# ESPC3_schematic.net
KiCad netlist of a schematic drawn in Altium Designer
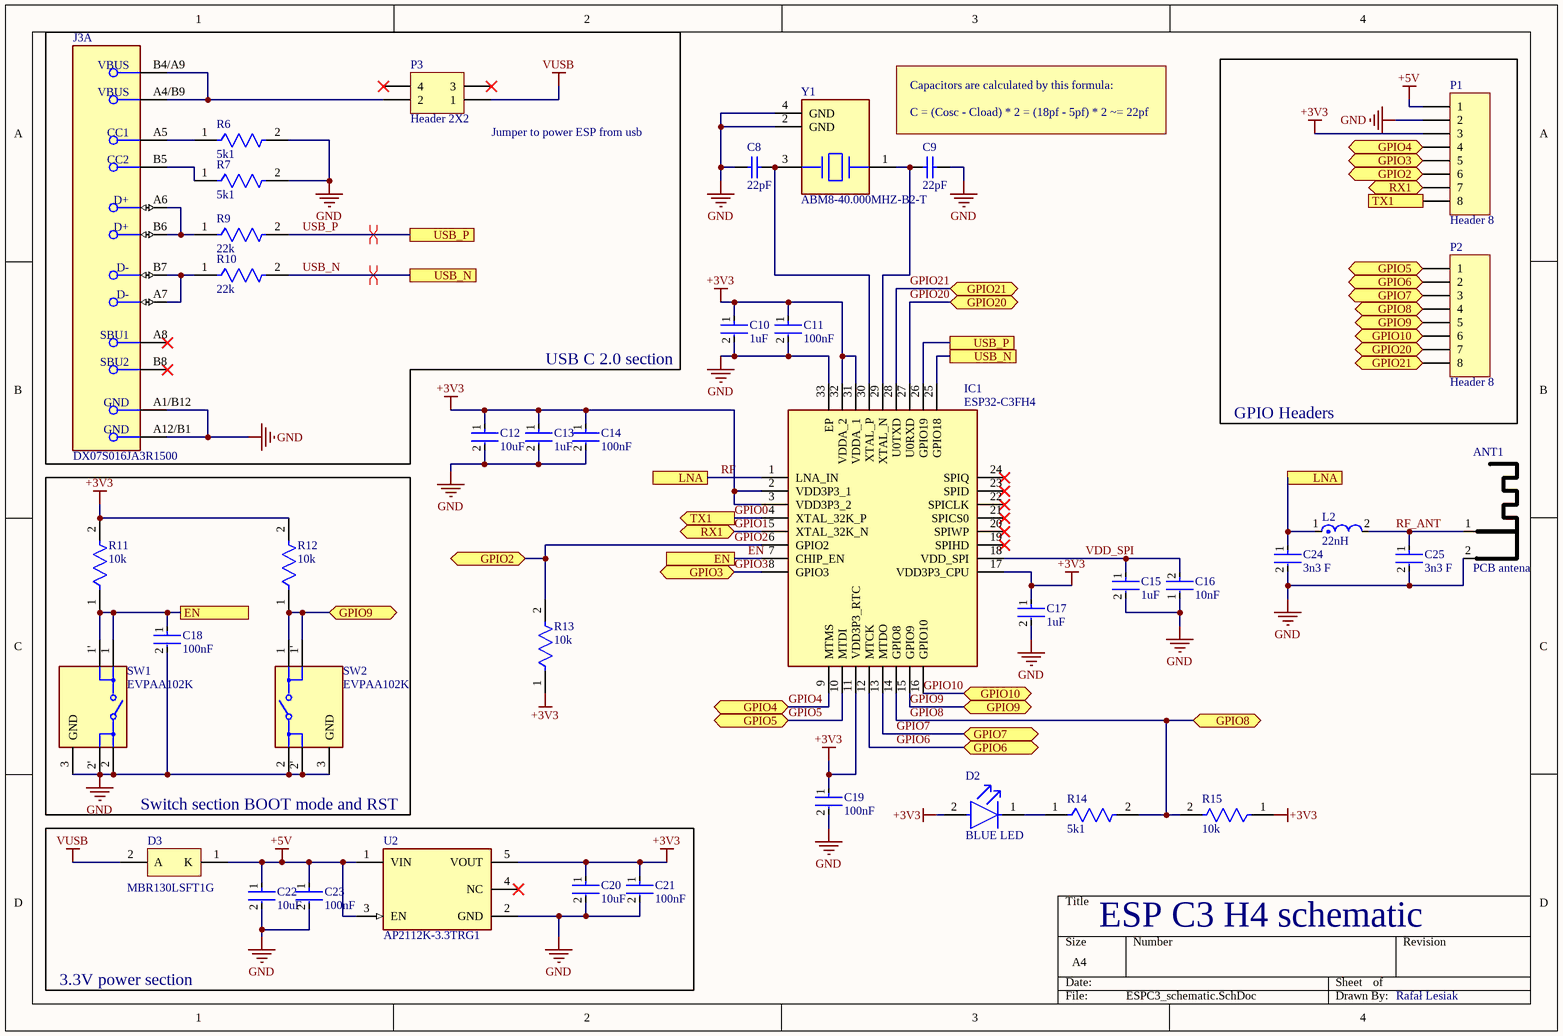
[diagram p0: ESPC3_schematic.SchDoc]

(export (version "E")
  (design (tool "Eeschema 10.0.6"))
  (components
    (comp (ref "ANT1")
      (value "PCB antena")
      (footprint "ANT_PCB_2_4GHz")
      (description "PCB antena 2.4GHz 50ohm from AN043 texas instrument")
      (libsource (lib "ANT_PCB_2_4_GHz") (part "ANT_PCB_2.4GHz"))
    )
    (comp (ref "C8")
      (value "22pF")
      (footprint "CAPC0603X33X15LL03T05")
      (fields
        (field (name "MANUFACTURER") "AVX Interconnect / Elco")
        (field (name "PART NUMBER") "0201YA220JAT2A")
      )
      (libsource (lib "Altium Content Vault") (part "CAP"))
    )
    (comp (ref "C9")
      (value "22pF")
      (footprint "CAPC0603X33X15LL03T05")
      (fields
        (field (name "MANUFACTURER") "AVX Interconnect / Elco")
        (field (name "PART NUMBER") "0201YA220JAT2A")
      )
      (libsource (lib "Altium Content Vault") (part "CAP"))
    )
    (comp (ref "C10")
      (value "1uF")
      (footprint "FP-GRM033-0_05-e01_0_2-MFG")
      (description "Chip Multilayer Ceramic Capacitors for General Purpose, 0201, 1.0uF, X5R, 15%, 20%, 10V")
      (libsource (lib "Altium Content Vault") (part "02cd4be3c70576c341d710602a673aa"))
    )
    (comp (ref "C11")
      (value "100nF")
      (footprint "FP-GRM033-0_03-MFG")
      (description "Chip Multilayer Ceramic Capacitors for General Purpose, 0201, 0.10uF, X7S, 22%, 10%, 10V")
      (fields (field (name "TOLERANCE") "10%"))
      (libsource (lib "Altium Content Vault") (part "b4654b650e69147ec39a6b967a45e02"))
    )
    (comp (ref "C12")
      (value "10uF")
      (footprint "FP-GRM155-0_2-IPC_A")
      (description "Chip Multilayer Ceramic Capacitors for General Purpose, 0402, 10uF, X5R, 15%, 20%, 10V")
      (libsource (lib "Altium Content Vault") (part "b4654b650e69147ec39a6b967a45e02"))
    )
    (comp (ref "C13")
      (value "1uF")
      (footprint "FP-GRM033-0_05-e01_0_2-MFG")
      (description "Chip Multilayer Ceramic Capacitors for General Purpose, 0201, 1.0uF, X5R, 15%, 20%, 10V")
      (libsource (lib "Altium Content Vault") (part "02cd4be3c70576c341d710602a673aa"))
    )
    (comp (ref "C14")
      (value "100nF")
      (footprint "FP-GRM033-0_03-MFG")
      (description "Chip Multilayer Ceramic Capacitors for General Purpose, 0201, 0.10uF, X7S, 22%, 10%, 10V")
      (fields (field (name "TOLERANCE") "10%"))
      (libsource (lib "Altium Content Vault") (part "b4654b650e69147ec39a6b967a45e02"))
    )
    (comp (ref "C15")
      (value "1uF")
      (footprint "FP-GRM033-0_05-e01_0_2-MFG")
      (description "Chip Multilayer Ceramic Capacitors for General Purpose, 0201, 1.0uF, X5R, 15%, 20%, 10V")
      (libsource (lib "Altium Content Vault") (part "02cd4be3c70576c341d710602a673aa"))
    )
    (comp (ref "C16")
      (value "10nF")
      (footprint "FP-GCM033-0_03-MFG")
      (description "Ceramic Capacitor for Automotive 10nF  ±10% 10VDC X7R 0201 Paper T/R")
      (fields (field (name "TOLERANCE") "10%"))
      (libsource (lib "Altium Content Vault") (part "f23184f103b6ebe33a8c269c53dcba6"))
    )
    (comp (ref "C17")
      (value "1uF")
      (footprint "FP-GRM033-0_05-e01_0_2-MFG")
      (description "Chip Multilayer Ceramic Capacitors for General Purpose, 0201, 1.0uF, X5R, 15%, 20%, 10V")
      (libsource (lib "Altium Content Vault") (part "02cd4be3c70576c341d710602a673aa"))
    )
    (comp (ref "C18")
      (value "100nF")
      (footprint "FP-GRM033-0_03-MFG")
      (description "Chip Multilayer Ceramic Capacitors for General Purpose, 0201, 0.10uF, X7S, 22%, 10%, 10V")
      (fields (field (name "TOLERANCE") "10%"))
      (libsource (lib "Altium Content Vault") (part "b4654b650e69147ec39a6b967a45e02"))
    )
    (comp (ref "C19")
      (value "100nF")
      (footprint "FP-GRM033-0_03-MFG")
      (description "Chip Multilayer Ceramic Capacitors for General Purpose, 0201, 0.10uF, X7S, 22%, 10%, 10V")
      (fields (field (name "TOLERANCE") "10%"))
      (libsource (lib "Altium Content Vault") (part "b4654b650e69147ec39a6b967a45e02"))
    )
    (comp (ref "C20")
      (value "10uF")
      (footprint "FP-GRM155-0_2-IPC_A")
      (description "Chip Multilayer Ceramic Capacitors for General Purpose, 0402, 10uF, X5R, 15%, 20%, 10V")
      (libsource (lib "Altium Content Vault") (part "b4654b650e69147ec39a6b967a45e02"))
    )
    (comp (ref "C21")
      (value "100nF")
      (footprint "FP-GRM033-0_03-MFG")
      (description "Chip Multilayer Ceramic Capacitors for General Purpose, 0201, 0.10uF, X7S, 22%, 10%, 10V")
      (fields (field (name "TOLERANCE") "10%"))
      (libsource (lib "Altium Content Vault") (part "b4654b650e69147ec39a6b967a45e02"))
    )
    (comp (ref "C22")
      (value "10uF")
      (footprint "FP-GRM155-0_2-IPC_A")
      (description "Chip Multilayer Ceramic Capacitors for General Purpose, 0402, 10uF, X5R, 15%, 20%, 10V")
      (libsource (lib "Altium Content Vault") (part "b4654b650e69147ec39a6b967a45e02"))
    )
    (comp (ref "C23")
      (value "100nF")
      (footprint "FP-GRM033-0_03-MFG")
      (description "Chip Multilayer Ceramic Capacitors for General Purpose, 0201, 0.10uF, X7S, 22%, 10%, 10V")
      (fields (field (name "TOLERANCE") "10%"))
      (libsource (lib "Altium Content Vault") (part "b4654b650e69147ec39a6b967a45e02"))
    )
    (comp (ref "C24")
      (value "3n3 F")
      (footprint "FP-GRM022-0_02-IPC_C")
      (description "Chip Multilayer Ceramic Capacitors for General Purpose, 01005, 3.3pF, C0G, 30ppm/°C, 0.25pF, 16V")
      (libsource (lib "Altium Content Vault") (part "02cd4be3c70576c341d710602a673aa"))
    )
    (comp (ref "C25")
      (value "3n3 F")
      (footprint "FP-GRM022-0_02-IPC_C")
      (description "Chip Multilayer Ceramic Capacitors for General Purpose, 01005, 3.3pF, C0G, 30ppm/°C, 0.25pF, 16V")
      (libsource (lib "Altium Content Vault") (part "02cd4be3c70576c341d710602a673aa"))
    )
    (comp (ref "D2")
      (value "BLUE LED")
      (footprint "FP-LTST-C191TBKT-MFG")
      (description "LED BLUE CLEAR CHIP SMD")
      (libsource (lib "Altium Content Vault") (part "8706943c75ba83719d021d2fdc84c58"))
    )
    (comp (ref "D3")
      (value "MBR130LSFT1G")
      (footprint "ONSC-SOD-123FL-2-498_V")
      (description "Schottky Power Rectifier, 2-Pin SOD-123, Pb-Free, Tape and Reel")
      (fields (field (name "MANUFACTURER") "On Semiconductor"))
      (libsource (lib "Altium Content Vault") (part "ONSC-D-K1A2-2_A"))
    )
    (comp (ref "IC1")
      (value "ESP32-C3FH4")
      (footprint "SamacSys:QFN50P500X500X90-33N-D")
      (description "Integrated Circuit")
      (fields (field (name "MOUSER PART NUMBER") "356-ESP32-C3FH4"))
      (libsource (lib "*") (part "ESP32-C3FH4"))
    )
    (comp (ref "J3")
      (value "DX07S016JA3R1500")
      (footprint "FP-DX07S016JA3R1500-MFG")
      (description "CONN RCP USB2.0 TYP C 24P SMD RA")
      (libsource (lib "Altium Content Vault") (part "86c7019cab7ffbad937e454fd6d8a8a"))
    )
    (comp (ref "L2")
      (value "22nH")
      (footprint "FP-LQP03PN_02-MFG")
      (description "Film type RF Inductor 22nH ±5% 140mA 2.85Ω 0201 (0603)")
      (fields (field (name "TOLERANCE") "5%"))
      (libsource (lib "Altium Content Vault") (part "ae3b6ca10b736fc74204ce580bf9b8e"))
    )
    (comp (ref "P1")
      (value "Header 8")
      (footprint "HDR1X8")
      (description "Header, 8-Pin")
      (fields (field (name "PUBLISHER") "Altium Limited"))
      (libsource (lib "Miscellaneous Connectors") (part "Header 8"))
    )
    (comp (ref "P2")
      (value "Header 8")
      (footprint "HDR1X8")
      (description "Header, 8-Pin")
      (fields (field (name "PUBLISHER") "Altium Limited"))
      (libsource (lib "Miscellaneous Connectors") (part "Header 8"))
    )
    (comp (ref "P3")
      (value "Header 2X2")
      (footprint "HDR2X2")
      (description "Header, 2-Pin, Dual row")
      (fields (field (name "PUBLISHER") "Altium Limited"))
      (libsource (lib "Miscellaneous Connectors") (part "Header 2X2"))
    )
    (comp (ref "R6")
      (value "5k1")
      (footprint "FP-AF0201-IPC_C")
      (description "Anti-Sulfurated Chip Resistors Automotive Grade 5.1kΩ 1% 200ppm/°C 0201")
      (fields (field (name "TOLERANCE") "1%"))
      (libsource (lib "Altium Content Vault") (part "1029c3af85768c4190bb7ad29bc67b5"))
    )
    (comp (ref "R7")
      (value "5k1")
      (footprint "FP-AF0201-IPC_C")
      (description "Anti-Sulfurated Chip Resistors Automotive Grade 5.1kΩ 1% 200ppm/°C 0201")
      (fields (field (name "TOLERANCE") "1%"))
      (libsource (lib "Altium Content Vault") (part "1029c3af85768c4190bb7ad29bc67b5"))
    )
    (comp (ref "R9")
      (value "22k")
      (footprint "FP-RMCF0201-IPC_B")
      (description "22kΩ ±5% 0.05W 0201 Thick Film Chip Resistor AEC-Q200 compliant")
      (fields (field (name "TOLERANCE") "5%"))
      (libsource (lib "Altium Content Vault") (part "1029c3af85768c4190bb7ad29bc67b5"))
    )
    (comp (ref "R10")
      (value "22k")
      (footprint "FP-RMCF0201-IPC_B")
      (description "22kΩ ±5% 0.05W 0201 Thick Film Chip Resistor AEC-Q200 compliant")
      (fields (field (name "TOLERANCE") "5%"))
      (libsource (lib "Altium Content Vault") (part "1029c3af85768c4190bb7ad29bc67b5"))
    )
    (comp (ref "R11")
      (value "10k")
      (footprint "FP-AC0402-IPC_C")
      (description "RES 10kΩ ±1% 0.125W 0402")
      (libsource (lib "Altium Content Vault") (part "1029c3af85768c4190bb7ad29bc67b5"))
    )
    (comp (ref "R12")
      (value "10k")
      (footprint "FP-AC0402-IPC_C")
      (description "RES 10kΩ ±1% 0.125W 0402")
      (libsource (lib "Altium Content Vault") (part "1029c3af85768c4190bb7ad29bc67b5"))
    )
    (comp (ref "R13")
      (value "10k")
      (footprint "FP-AC0402-IPC_C")
      (description "RES 10kΩ ±1% 0.125W 0402")
      (libsource (lib "Altium Content Vault") (part "1029c3af85768c4190bb7ad29bc67b5"))
    )
    (comp (ref "R14")
      (value "5k1")
      (footprint "FP-AF0201-IPC_C")
      (description "Anti-Sulfurated Chip Resistors Automotive Grade 5.1kΩ 1% 200ppm/°C 0201")
      (fields (field (name "TOLERANCE") "1%"))
      (libsource (lib "Altium Content Vault") (part "1029c3af85768c4190bb7ad29bc67b5"))
    )
    (comp (ref "R15")
      (value "10k")
      (footprint "FP-AC0402-IPC_C")
      (description "RES 10kΩ ±1% 0.125W 0402")
      (libsource (lib "Altium Content Vault") (part "1029c3af85768c4190bb7ad29bc67b5"))
    )
    (comp (ref "SW1")
      (value "EVPAA102K")
      (footprint "FP-EVPAA102K-MFG")
      (description "EVPAA102K Switch Tactile N.O. SPST Rectangular Button J-Bend 0.02A 15VDC 1N SMD Embossed T/R")
      (libsource (lib "") (part "006f0cc0644a2080297537bd5f30309_1"))
    )
    (comp (ref "SW2")
      (value "EVPAA102K")
      (footprint "FP-EVPAA102K-MFG")
      (description "EVPAA102K Switch Tactile N.O. SPST Rectangular Button J-Bend 0.02A 15VDC 1N SMD Embossed T/R")
      (libsource (lib "Altium Content Vault") (part "006f0cc0644a2080297537bd5f30309"))
    )
    (comp (ref "U2")
      (value "AP2112K-3.3TRG1")
      (footprint "FP-SOT25-IPC_A")
      (description "IC REG LINEAR 3.3V 600MA SOT25")
      (libsource (lib "Altium Content Vault") (part "c8ab751aee5229183125ab046a11caa"))
    )
    (comp (ref "Y1")
      (value "ABM8-40.000MHZ-B2-T")
      (footprint "FP-ABM8-MFG")
      (description "Crystal 40MHz ±20ppm 18pF SMD-4 3.2mm x 2.5mm")
      (fields (field (name "TOLERANCE") "20ppm"))
      (libsource (lib "Altium Content Vault") (part "dfdb7f9a12507849fb681da9a70121c"))
    )
  )
  (nets
    (net (code "1") (name "+3V3") (class "Default")
      (node (ref "C10") (pin "1") (pinfunction "1_1") (pintype "passive"))
      (node (ref "C11") (pin "1") (pinfunction "1_1") (pintype "passive"))
      (node (ref "C12") (pin "1") (pinfunction "1_1") (pintype "passive"))
      (node (ref "C13") (pin "1") (pinfunction "1_1") (pintype "passive"))
      (node (ref "C14") (pin "1") (pinfunction "1_1") (pintype "passive"))
      (node (ref "C17") (pin "1") (pinfunction "1_1") (pintype "passive"))
      (node (ref "C19") (pin "1") (pinfunction "1_1") (pintype "passive"))
      (node (ref "C20") (pin "1") (pinfunction "1_1") (pintype "passive"))
      (node (ref "C21") (pin "1") (pinfunction "1_1") (pintype "passive"))
      (node (ref "D2") (pin "2") (pinfunction "A_2") (pintype "passive"))
      (node (ref "IC1") (pin "11") (pinfunction "VDD3P3_RTC_11") (pintype "passive"))
      (node (ref "IC1") (pin "17") (pinfunction "VDD3P3_CPU_17") (pintype "passive"))
      (node (ref "IC1") (pin "2") (pinfunction "VDD3P3_1_2") (pintype "passive"))
      (node (ref "IC1") (pin "3") (pinfunction "VDD3P3_2_3") (pintype "passive"))
      (node (ref "IC1") (pin "31") (pinfunction "VDDA_1_31") (pintype "passive"))
      (node (ref "IC1") (pin "32") (pinfunction "VDDA_2_32") (pintype "passive"))
      (node (ref "P1") (pin "3") (pinfunction "3_3") (pintype "passive"))
      (node (ref "R11") (pin "2") (pinfunction "2_2") (pintype "passive"))
      (node (ref "R12") (pin "2") (pinfunction "2_2") (pintype "passive"))
      (node (ref "R13") (pin "1") (pinfunction "1_1") (pintype "passive"))
      (node (ref "R15") (pin "1") (pinfunction "1_1") (pintype "passive"))
      (node (ref "U2") (pin "5") (pinfunction "VOUT_5") (pintype "power_in"))
    )
    (net (code "2") (name "+5V") (class "Default")
      (node (ref "C22") (pin "1") (pinfunction "1_1") (pintype "passive"))
      (node (ref "C23") (pin "1") (pinfunction "1_1") (pintype "passive"))
      (node (ref "D3") (pin "1") (pinfunction "K_1") (pintype "passive"))
      (node (ref "P1") (pin "1") (pinfunction "1_1") (pintype "passive"))
      (node (ref "U2") (pin "1") (pinfunction "VIN_1") (pintype "power_in"))
      (node (ref "U2") (pin "3") (pinfunction "EN_3") (pintype "input"))
    )
    (net (code "3") (name "/EN") (class "Default")
      (node (ref "C18") (pin "1") (pinfunction "1_1") (pintype "passive"))
      (node (ref "IC1") (pin "7") (pinfunction "CHIP_EN_7") (pintype "passive"))
      (node (ref "R11") (pin "1") (pinfunction "1_1") (pintype "passive"))
      (node (ref "SW1") (pin "1") (pinfunction "1_1") (pintype "passive"))
      (node (ref "SW1") (pin "1'") (pinfunction "1'_1'") (pintype "passive"))
    )
    (net (code "4") (name "/GPIO0") (class "Default")
      (node (ref "IC1") (pin "4") (pinfunction "XTAL_32K_P_4") (pintype "passive"))
      (node (ref "P1") (pin "8") (pinfunction "8_8") (pintype "passive"))
    )
    (net (code "5") (name "/GPIO1") (class "Default")
      (node (ref "IC1") (pin "5") (pinfunction "XTAL_32K_N_5") (pintype "passive"))
      (node (ref "P1") (pin "7") (pinfunction "7_7") (pintype "passive"))
    )
    (net (code "6") (name "/GPIO2") (class "Default")
      (node (ref "IC1") (pin "6") (pinfunction "GPIO2_6") (pintype "passive"))
      (node (ref "P1") (pin "6") (pinfunction "6_6") (pintype "passive"))
      (node (ref "R13") (pin "2") (pinfunction "2_2") (pintype "passive"))
    )
    (net (code "7") (name "/GPIO3") (class "Default")
      (node (ref "IC1") (pin "8") (pinfunction "GPIO3_8") (pintype "passive"))
      (node (ref "P1") (pin "5") (pinfunction "5_5") (pintype "passive"))
    )
    (net (code "8") (name "/GPIO4") (class "Default")
      (node (ref "IC1") (pin "9") (pinfunction "MTMS_9") (pintype "passive"))
      (node (ref "P1") (pin "4") (pinfunction "4_4") (pintype "passive"))
    )
    (net (code "9") (name "/GPIO5") (class "Default")
      (node (ref "IC1") (pin "10") (pinfunction "MTDI_10") (pintype "passive"))
      (node (ref "P2") (pin "1") (pinfunction "1_1") (pintype "passive"))
    )
    (net (code "10") (name "/GPIO6") (class "Default")
      (node (ref "IC1") (pin "12") (pinfunction "MTCK_12") (pintype "passive"))
      (node (ref "P2") (pin "2") (pinfunction "2_2") (pintype "passive"))
    )
    (net (code "11") (name "/GPIO7") (class "Default")
      (node (ref "IC1") (pin "13") (pinfunction "MTDO_13") (pintype "passive"))
      (node (ref "P2") (pin "3") (pinfunction "3_3") (pintype "passive"))
    )
    (net (code "12") (name "/GPIO8") (class "Default")
      (node (ref "IC1") (pin "14") (pinfunction "GPIO8_14") (pintype "passive"))
      (node (ref "P2") (pin "4") (pinfunction "4_4") (pintype "passive"))
      (node (ref "R14") (pin "2") (pinfunction "2_2") (pintype "passive"))
      (node (ref "R15") (pin "2") (pinfunction "2_2") (pintype "passive"))
    )
    (net (code "13") (name "/GPIO9") (class "Default")
      (node (ref "IC1") (pin "15") (pinfunction "GPIO9_15") (pintype "passive"))
      (node (ref "P2") (pin "5") (pinfunction "5_5") (pintype "passive"))
      (node (ref "R12") (pin "1") (pinfunction "1_1") (pintype "passive"))
      (node (ref "SW2") (pin "1") (pinfunction "1_1") (pintype "passive"))
      (node (ref "SW2") (pin "1'") (pinfunction "1'_1'") (pintype "passive"))
    )
    (net (code "14") (name "/GPIO10") (class "Default")
      (node (ref "IC1") (pin "16") (pinfunction "GPIO10_16") (pintype "passive"))
      (node (ref "P2") (pin "6") (pinfunction "6_6") (pintype "passive"))
    )
    (net (code "15") (name "/GPIO20") (class "Default")
      (node (ref "IC1") (pin "27") (pinfunction "U0RXD_27") (pintype "passive"))
      (node (ref "P2") (pin "7") (pinfunction "7_7") (pintype "passive"))
    )
    (net (code "16") (name "/GPIO21") (class "Default")
      (node (ref "IC1") (pin "28") (pinfunction "U0TXD_28") (pintype "passive"))
      (node (ref "P2") (pin "8") (pinfunction "8_8") (pintype "passive"))
    )
    (net (code "17") (name "/RF") (class "Default")
      (node (ref "C24") (pin "1") (pinfunction "1_1") (pintype "passive"))
      (node (ref "IC1") (pin "1") (pinfunction "LNA_IN_1") (pintype "passive"))
      (node (ref "L2") (pin "1") (pinfunction "1_1") (pintype "passive"))
    )
    (net (code "18") (name "/RF_ANT") (class "Default")
      (node (ref "ANT1") (pin "1") (pinfunction "RF_1") (pintype "passive"))
      (node (ref "C25") (pin "1") (pinfunction "1_1") (pintype "passive"))
      (node (ref "L2") (pin "2") (pinfunction "2_2") (pintype "passive"))
    )
    (net (code "19") (name "/USB_N") (class "Default")
      (node (ref "IC1") (pin "25") (pinfunction "GPIO18_25") (pintype "passive"))
      (node (ref "R10") (pin "2") (pinfunction "2_2") (pintype "passive"))
    )
    (net (code "20") (name "/USB_P") (class "Default")
      (node (ref "IC1") (pin "26") (pinfunction "GPIO19_26") (pintype "passive"))
      (node (ref "R9") (pin "2") (pinfunction "2_2") (pintype "passive"))
    )
    (net (code "21") (name "/VDD_SPI") (class "Default")
      (node (ref "C15") (pin "1") (pinfunction "1_1") (pintype "passive"))
      (node (ref "C16") (pin "2") (pinfunction "2_2") (pintype "passive"))
      (node (ref "IC1") (pin "18") (pinfunction "VDD_SPI_18") (pintype "passive"))
    )
    (net (code "22") (name "GND") (class "Default")
      (node (ref "ANT1") (pin "2") (pinfunction "GND_2") (pintype "passive"))
      (node (ref "C10") (pin "2") (pinfunction "2_2") (pintype "passive"))
      (node (ref "C11") (pin "2") (pinfunction "2_2") (pintype "passive"))
      (node (ref "C12") (pin "2") (pinfunction "2_2") (pintype "passive"))
      (node (ref "C13") (pin "2") (pinfunction "2_2") (pintype "passive"))
      (node (ref "C14") (pin "2") (pinfunction "2_2") (pintype "passive"))
      (node (ref "C15") (pin "2") (pinfunction "2_2") (pintype "passive"))
      (node (ref "C16") (pin "1") (pinfunction "1_1") (pintype "passive"))
      (node (ref "C17") (pin "2") (pinfunction "2_2") (pintype "passive"))
      (node (ref "C18") (pin "2") (pinfunction "2_2") (pintype "passive"))
      (node (ref "C19") (pin "2") (pinfunction "2_2") (pintype "passive"))
      (node (ref "C20") (pin "2") (pinfunction "2_2") (pintype "passive"))
      (node (ref "C21") (pin "2") (pinfunction "2_2") (pintype "passive"))
      (node (ref "C22") (pin "2") (pinfunction "2_2") (pintype "passive"))
      (node (ref "C23") (pin "2") (pinfunction "2_2") (pintype "passive"))
      (node (ref "C24") (pin "2") (pinfunction "2_2") (pintype "passive"))
      (node (ref "C25") (pin "2") (pinfunction "2_2") (pintype "passive"))
      (node (ref "C8") (pin "1") (pinfunction "1_1") (pintype "passive"))
      (node (ref "C9") (pin "2") (pinfunction "2_2") (pintype "passive"))
      (node (ref "IC1") (pin "33") (pinfunction "EP_33") (pintype "passive"))
      (node (ref "J3") (pin "A1/B12") (pinfunction "GND_A1/B12") (pintype "power_in"))
      (node (ref "J3") (pin "A12/B1") (pinfunction "GND_A12/B1") (pintype "power_in"))
      (node (ref "P1") (pin "2") (pinfunction "2_2") (pintype "passive"))
      (node (ref "R6") (pin "2") (pinfunction "2_2") (pintype "passive"))
      (node (ref "R7") (pin "2") (pinfunction "2_2") (pintype "passive"))
      (node (ref "SW1") (pin "2") (pinfunction "2_2") (pintype "passive"))
      (node (ref "SW1") (pin "2'") (pinfunction "2'_2'") (pintype "passive"))
      (node (ref "SW1") (pin "3") (pinfunction "GND_3") (pintype "power_in"))
      (node (ref "SW2") (pin "2") (pinfunction "2_2") (pintype "passive"))
      (node (ref "SW2") (pin "2'") (pinfunction "2'_2'") (pintype "passive"))
      (node (ref "SW2") (pin "3") (pinfunction "GND_3") (pintype "power_in"))
      (node (ref "U2") (pin "2") (pinfunction "GND_2") (pintype "power_in"))
      (node (ref "Y1") (pin "2") (pinfunction "GND_2") (pintype "power_in"))
      (node (ref "Y1") (pin "4") (pinfunction "GND_4") (pintype "power_in"))
    )
    (net (code "23") (name "Net-(D2-C)") (class "Default")
      (node (ref "D2") (pin "1") (pinfunction "C_1") (pintype "passive"))
      (node (ref "R14") (pin "1") (pinfunction "1_1") (pintype "passive"))
    )
    (net (code "24") (name "Net-(IC1-XTAL_N)") (class "Default")
      (node (ref "C9") (pin "1") (pinfunction "1_1") (pintype "passive"))
      (node (ref "IC1") (pin "29") (pinfunction "XTAL_N_29") (pintype "passive"))
      (node (ref "Y1") (pin "1") (pinfunction "1_1") (pintype "passive"))
    )
    (net (code "25") (name "Net-(IC1-XTAL_P)") (class "Default")
      (node (ref "C8") (pin "2") (pinfunction "2_2") (pintype "passive"))
      (node (ref "IC1") (pin "30") (pinfunction "XTAL_P_30") (pintype "passive"))
      (node (ref "Y1") (pin "3") (pinfunction "3_3") (pintype "passive"))
    )
    (net (code "26") (name "Net-(J3A-CC1)") (class "Default")
      (node (ref "J3") (pin "A5") (pinfunction "CC1_A5") (pintype "passive"))
      (node (ref "R6") (pin "1") (pinfunction "1_1") (pintype "passive"))
    )
    (net (code "27") (name "Net-(J3A-CC2)") (class "Default")
      (node (ref "J3") (pin "B5") (pinfunction "CC2_B5") (pintype "passive"))
      (node (ref "R7") (pin "1") (pinfunction "1_1") (pintype "passive"))
    )
    (net (code "28") (name "Net-(J3A-D+-PadA6)") (class "Default")
      (node (ref "J3") (pin "A6") (pinfunction "D+_A6") (pintype "bidirectional"))
      (node (ref "J3") (pin "B6") (pinfunction "D+_B6") (pintype "bidirectional"))
      (node (ref "R9") (pin "1") (pinfunction "1_1") (pintype "passive"))
    )
    (net (code "29") (name "Net-(J3A-D--PadA7)") (class "Default")
      (node (ref "J3") (pin "A7") (pinfunction "D-_A7") (pintype "bidirectional"))
      (node (ref "J3") (pin "B7") (pinfunction "D-_B7") (pintype "bidirectional"))
      (node (ref "R10") (pin "1") (pinfunction "1_1") (pintype "passive"))
    )
    (net (code "30") (name "Net-(J3A-VBUS-PadA4{slash}B9)") (class "Default")
      (node (ref "J3") (pin "A4/B9") (pinfunction "VBUS_A4/B9") (pintype "power_in"))
      (node (ref "J3") (pin "B4/A9") (pinfunction "VBUS_B4/A9") (pintype "power_in"))
      (node (ref "P3") (pin "2") (pinfunction "2_2") (pintype "passive"))
    )
    (net (code "31") (name "VUSB") (class "Default")
      (node (ref "D3") (pin "2") (pinfunction "A_2") (pintype "passive"))
      (node (ref "P3") (pin "1") (pinfunction "1_1") (pintype "passive"))
    )
    (net (code "32") (name "unconnected-(IC1-SPICLK-Pad22)") (class "Default")
      (node (ref "IC1") (pin "22") (pinfunction "SPICLK_22") (pintype "passive+no_connect"))
    )
    (net (code "33") (name "unconnected-(IC1-SPICS0-Pad21)") (class "Default")
      (node (ref "IC1") (pin "21") (pinfunction "SPICS0_21") (pintype "passive+no_connect"))
    )
    (net (code "34") (name "unconnected-(IC1-SPID-Pad23)") (class "Default")
      (node (ref "IC1") (pin "23") (pinfunction "SPID_23") (pintype "passive+no_connect"))
    )
    (net (code "35") (name "unconnected-(IC1-SPIHD-Pad19)") (class "Default")
      (node (ref "IC1") (pin "19") (pinfunction "SPIHD_19") (pintype "passive+no_connect"))
    )
    (net (code "36") (name "unconnected-(IC1-SPIQ-Pad24)") (class "Default")
      (node (ref "IC1") (pin "24") (pinfunction "SPIQ_24") (pintype "passive+no_connect"))
    )
    (net (code "37") (name "unconnected-(IC1-SPIWP-Pad20)") (class "Default")
      (node (ref "IC1") (pin "20") (pinfunction "SPIWP_20") (pintype "passive+no_connect"))
    )
    (net (code "38") (name "unconnected-(J3A-SBU1-PadA8)") (class "Default")
      (node (ref "J3") (pin "A8") (pinfunction "SBU1_A8") (pintype "passive+no_connect"))
    )
    (net (code "39") (name "unconnected-(J3A-SBU2-PadB8)") (class "Default")
      (node (ref "J3") (pin "B8") (pinfunction "SBU2_B8") (pintype "passive+no_connect"))
    )
    (net (code "40") (name "unconnected-(P3-Pad3)") (class "Default")
      (node (ref "P3") (pin "3") (pinfunction "3_3") (pintype "passive+no_connect"))
    )
    (net (code "41") (name "unconnected-(P3-Pad4)") (class "Default")
      (node (ref "P3") (pin "4") (pinfunction "4_4") (pintype "passive+no_connect"))
    )
    (net (code "42") (name "unconnected-(U2-NC-Pad4)") (class "Default")
      (node (ref "U2") (pin "4") (pinfunction "NC_4") (pintype "passive+no_connect"))
    )
  )
)
